# QCopterFCs_Sch.net
KiCad netlist of a schematic drawn in Altium Designer
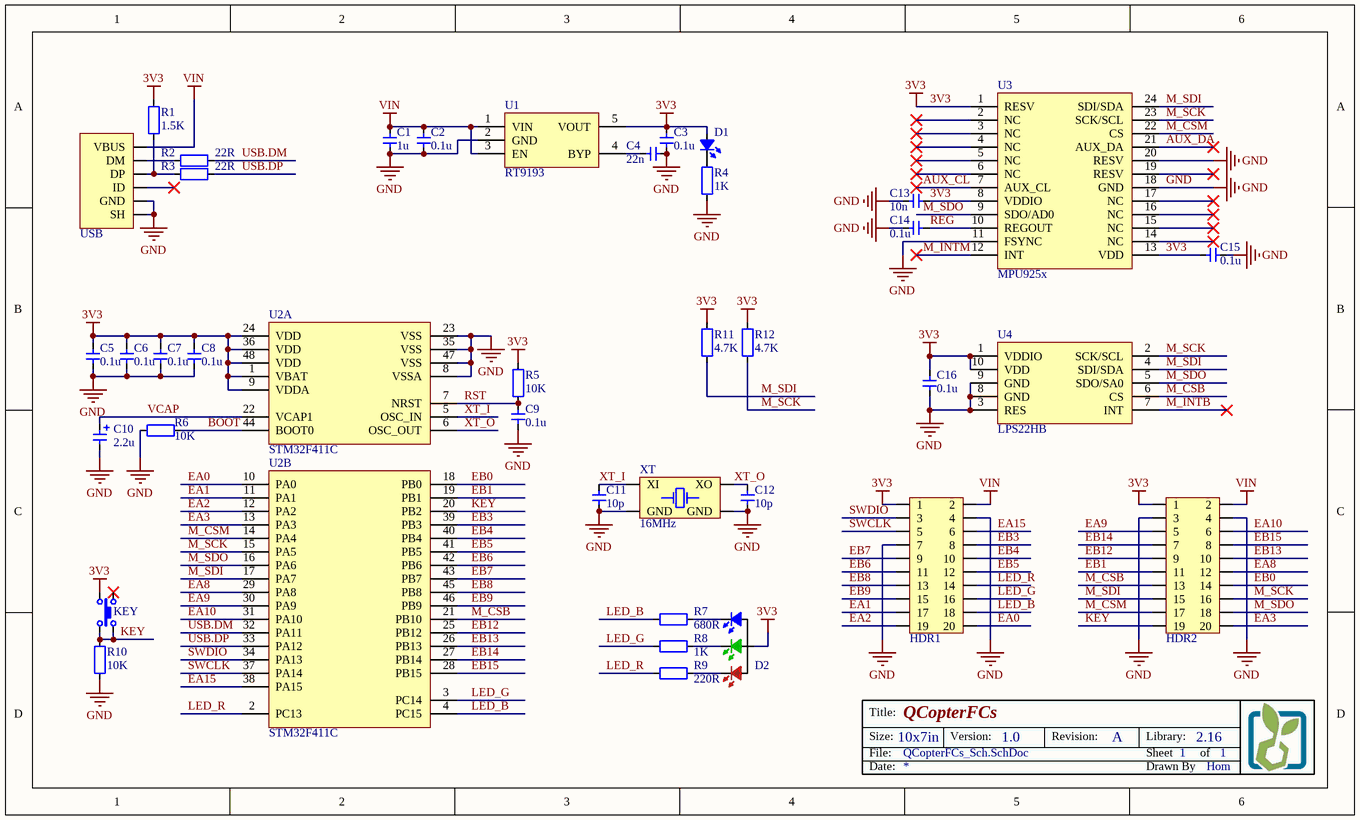
[diagram p0: QCopterFCs_Sch.SchDoc]

(export (version "E")
  (design (tool "Eeschema 10.0.6"))
  (components
    (comp (ref "C1")
      (value "1u")
      (footprint "PCB_PassiveCap:CAP_0603")
      (description "Capacitor")
      (fields (field (name "Comment") "Cap_0603"))
      (libsource (lib "SCH_Passive") (part "Cap_0603"))
    )
    (comp (ref "C2")
      (value "0.1u")
      (footprint "PCB_PassiveCap:CAP_0603")
      (description "Capacitor")
      (fields (field (name "Comment") "Cap_0603"))
      (libsource (lib "SCH_Passive") (part "Cap_0603"))
    )
    (comp (ref "C3")
      (value "0.1u")
      (footprint "PCB_PassiveCap:CAP_0603")
      (description "Capacitor")
      (fields (field (name "Comment") "Cap_0603"))
      (libsource (lib "SCH_Passive") (part "Cap_0603"))
    )
    (comp (ref "C4")
      (value "22n")
      (footprint "PCB_PassiveCap:CAP_0603")
      (description "Capacitor")
      (fields (field (name "Comment") "Cap_0603"))
      (libsource (lib "SCH_Passive") (part "Cap_0603"))
    )
    (comp (ref "C5")
      (value "0.1u")
      (footprint "PCB_PassiveCap:CAP_0402")
      (description "Capacitor")
      (fields (field (name "Comment") "Cap_0402"))
      (libsource (lib "SCH_Passive") (part "Cap_0402"))
    )
    (comp (ref "C6")
      (value "0.1u")
      (footprint "PCB_PassiveCap:CAP_0402")
      (description "Capacitor")
      (fields (field (name "Comment") "Cap_0402"))
      (libsource (lib "SCH_Passive") (part "Cap_0402"))
    )
    (comp (ref "C7")
      (value "0.1u")
      (footprint "PCB_PassiveCap:CAP_0402")
      (description "Capacitor")
      (fields (field (name "Comment") "Cap_0402"))
      (libsource (lib "SCH_Passive") (part "Cap_0402"))
    )
    (comp (ref "C8")
      (value "0.1u")
      (footprint "PCB_PassiveCap:CAP_0402")
      (description "Capacitor")
      (fields (field (name "Comment") "Cap_0402"))
      (libsource (lib "SCH_Passive") (part "Cap_0402"))
    )
    (comp (ref "C9")
      (value "0.1u")
      (footprint "PCB_PassiveCap:CAP_0402")
      (description "Capacitor")
      (fields (field (name "Comment") "Cap_0402"))
      (libsource (lib "SCH_Passive") (part "Cap_0402"))
    )
    (comp (ref "C10")
      (value "2.2u")
      (footprint "PCB_PassiveCap:CAP_TAN_P0805")
      (description "Capacitor")
      (fields (field (name "Comment") "Cap_Tan_0805"))
      (libsource (lib "SCH_Passive") (part "Cap_Tan_0805"))
    )
    (comp (ref "C11")
      (value "10p")
      (footprint "PCB_PassiveCap:CAP_0402")
      (description "Capacitor")
      (fields (field (name "Comment") "Cap_0402"))
      (libsource (lib "SCH_Passive") (part "Cap_0402"))
    )
    (comp (ref "C12")
      (value "10p")
      (footprint "PCB_PassiveCap:CAP_0402")
      (description "Capacitor")
      (fields (field (name "Comment") "Cap_0402"))
      (libsource (lib "SCH_Passive") (part "Cap_0402"))
    )
    (comp (ref "C13")
      (value "10n")
      (footprint "PCB_PassiveCap:CAP_0402")
      (description "Capacitor")
      (fields (field (name "Comment") "Cap_0402"))
      (libsource (lib "SCH_Passive") (part "Cap_0402"))
    )
    (comp (ref "C14")
      (value "0.1u")
      (footprint "PCB_PassiveCap:CAP_0402")
      (description "Capacitor")
      (fields (field (name "Comment") "Cap_0402"))
      (libsource (lib "SCH_Passive") (part "Cap_0402"))
    )
    (comp (ref "C15")
      (value "0.1u")
      (footprint "PCB_PassiveCap:CAP_0402")
      (description "Capacitor")
      (fields (field (name "Comment") "Cap_0402"))
      (libsource (lib "SCH_Passive") (part "Cap_0402"))
    )
    (comp (ref "C16")
      (value "0.1u")
      (footprint "PCB_PassiveCap:CAP_0402")
      (description "Capacitor")
      (fields (field (name "Comment") "Cap_0402"))
      (libsource (lib "SCH_Passive") (part "Cap_0402"))
    )
    (comp (ref "D1")
      (value "LED_0603")
      (footprint "PCB_ActiveLED:LED_0603_YELLOW")
      (description "LED")
      (libsource (lib "SCH_Active") (part "LED_0603"))
    )
    (comp (ref "D2")
      (value "LED_1616_RGB")
      (footprint "PCB_ActiveLED:LED_1616_RGB")
      (description "LED")
      (libsource (lib "SCH_Active") (part "LED_1616_RGB"))
    )
    (comp (ref "HDR1")
      (value "HDR2x10_1.27")
      (footprint "PCB_ConnectorHDR:HDR2X10_1.27_180S")
      (description "Header")
      (libsource (lib "SCH_ConnectorHDR") (part "HDR2x10_1.27"))
    )
    (comp (ref "HDR2")
      (value "HDR2x10_1.27")
      (footprint "PCB_ConnectorHDR:HDR2X10_1.27_180S")
      (description "Header")
      (libsource (lib "SCH_ConnectorHDR") (part "HDR2x10_1.27"))
    )
    (comp (ref "KEY")
      (value "ButtonTACT")
      (footprint "PCB_Switch:ButtonTACT_3.5*3.55_90")
      (description "Button")
      (libsource (lib "SCH_Switch") (part "ButtonTACT"))
    )
    (comp (ref "R1")
      (value "1.5K")
      (footprint "PCB_PassiveRes:RES_0402")
      (description "Resistor")
      (fields (field (name "Comment") "Res_0402"))
      (libsource (lib "") (part "Res_0402_1"))
    )
    (comp (ref "R2")
      (value "22R")
      (footprint "PCB_PassiveRes:RES_0402")
      (description "Resistor")
      (fields (field (name "Comment") "Res_0402"))
      (libsource (lib "") (part "Res_0402_3"))
    )
    (comp (ref "R3")
      (value "22R")
      (footprint "PCB_PassiveRes:RES_0402")
      (description "Resistor")
      (fields (field (name "Comment") "Res_0402"))
      (libsource (lib "") (part "Res_0402_3"))
    )
    (comp (ref "R4")
      (value "1K")
      (footprint "PCB_PassiveRes:RES_0603")
      (description "Resistor")
      (fields (field (name "Comment") "Res_0603"))
      (libsource (lib "SCH_Passive") (part "Res_0603"))
    )
    (comp (ref "R5")
      (value "10K")
      (footprint "PCB_PassiveRes:RES_0402")
      (description "Resistor")
      (fields (field (name "Comment") "Res_0402"))
      (libsource (lib "") (part "Res_0402_2"))
    )
    (comp (ref "R6")
      (value "10K")
      (footprint "PCB_PassiveRes:RES_0402")
      (description "Resistor")
      (fields (field (name "Comment") "Res_0402"))
      (libsource (lib "SCH_Passive") (part "Res_0402"))
    )
    (comp (ref "R7")
      (value "680R")
      (footprint "PCB_PassiveRes:RES_0402")
      (description "Resistor")
      (fields (field (name "Comment") "Res_0402"))
      (libsource (lib "") (part "Res_0402_3"))
    )
    (comp (ref "R8")
      (value "1K")
      (footprint "PCB_PassiveRes:RES_0402")
      (description "Resistor")
      (fields (field (name "Comment") "Res_0402"))
      (libsource (lib "") (part "Res_0402_3"))
    )
    (comp (ref "R9")
      (value "220R")
      (footprint "PCB_PassiveRes:RES_0402")
      (description "Resistor")
      (fields (field (name "Comment") "Res_0402"))
      (libsource (lib "") (part "Res_0402_3"))
    )
    (comp (ref "R10")
      (value "10K")
      (footprint "PCB_PassiveRes:RES_0402")
      (description "Resistor")
      (fields (field (name "Comment") "Res_0402"))
      (libsource (lib "") (part "Res_0402_2"))
    )
    (comp (ref "R11")
      (value "4.7K")
      (footprint "PCB_PassiveRes:RES_0402")
      (description "Resistor")
      (fields (field (name "Comment") "Res_0402"))
      (libsource (lib "") (part "Res_0402_2"))
    )
    (comp (ref "R12")
      (value "4.7K")
      (footprint "PCB_PassiveRes:RES_0402")
      (description "Resistor")
      (fields (field (name "Comment") "Res_0402"))
      (libsource (lib "") (part "Res_0402_2"))
    )
    (comp (ref "U1")
      (value "RT9193")
      (footprint "PCB_IntegratedCircuit:SOT23-5")
      (description "Power")
      (libsource (lib "SCH_IntegratedCircuit") (part "RT9193"))
    )
    (comp (ref "U2")
      (value "STM32F411C")
      (footprint "PCB_IntegratedCircuit:QFN_P0.5_48")
      (description "MCU")
      (libsource (lib "SCH_IntegratedCircuit") (part "STM32F4x1C"))
    )
    (comp (ref "U3")
      (value "MPU925x")
      (footprint "PCB_IntegratedCircuit:QFN_P0.4_24")
      (description "Sensor Motion")
      (libsource (lib "SCH_IntegratedCircuit") (part "MPU925x"))
    )
    (comp (ref "U4")
      (value "LPS22HB")
      (footprint "PCB_IntegratedCircuit:HCLGA-2x2_10")
      (description "Sensor Pressure")
      (libsource (lib "SCH_IntegratedCircuit") (part "LPS22HB"))
    )
    (comp (ref "USB")
      (value "USB_Micro")
      (footprint "PCB_USB:USB_Micro-AB")
      (description "USB")
      (libsource (lib "SCH_USB") (part "USB_Micro"))
    )
    (comp (ref "XT")
      (value "16MHz")
      (footprint "PCB_Oscillator:XT_2520_4")
      (description "Crystal Oscillator")
      (fields (field (name "Comment") "XTAL_2520_4P"))
      (libsource (lib "SCH_Oscillator") (part "XTAL_2520_4P"))
    )
  )
  (nets
    (net (code "1") (name "/AUX_CL") (class "Default")
      (node (ref "U3") (pin "7") (pinfunction "AUX_CL_7") (pintype "passive+no_connect"))
    )
    (net (code "2") (name "/AUX_DA") (class "Default")
      (node (ref "U3") (pin "21") (pinfunction "AUX_DA_21") (pintype "passive+no_connect"))
    )
    (net (code "3") (name "/BOOT") (class "Default")
      (node (ref "R6") (pin "2") (pinfunction "2_2") (pintype "passive"))
      (node (ref "U2") (pin "44") (pinfunction "BOOT0_44") (pintype "passive"))
    )
    (net (code "4") (name "/EA0") (class "Default")
      (node (ref "HDR1") (pin "20") (pinfunction "20_20") (pintype "passive"))
      (node (ref "U2") (pin "10") (pinfunction "PA0_10") (pintype "passive"))
    )
    (net (code "5") (name "/EA1") (class "Default")
      (node (ref "HDR1") (pin "17") (pinfunction "17_17") (pintype "passive"))
      (node (ref "U2") (pin "11") (pinfunction "PA1_11") (pintype "passive"))
    )
    (net (code "6") (name "/EA2") (class "Default")
      (node (ref "HDR1") (pin "19") (pinfunction "19_19") (pintype "passive"))
      (node (ref "U2") (pin "12") (pinfunction "PA2_12") (pintype "passive"))
    )
    (net (code "7") (name "/EA3") (class "Default")
      (node (ref "HDR2") (pin "20") (pinfunction "20_20") (pintype "passive"))
      (node (ref "U2") (pin "13") (pinfunction "PA3_13") (pintype "passive"))
    )
    (net (code "8") (name "/EA8") (class "Default")
      (node (ref "HDR2") (pin "12") (pinfunction "12_12") (pintype "passive"))
      (node (ref "U2") (pin "29") (pinfunction "PA8_29") (pintype "passive"))
    )
    (net (code "9") (name "/EA9") (class "Default")
      (node (ref "HDR2") (pin "5") (pinfunction "5_5") (pintype "passive"))
      (node (ref "U2") (pin "30") (pinfunction "PA9_30") (pintype "passive"))
    )
    (net (code "10") (name "/EA10") (class "Default")
      (node (ref "HDR2") (pin "6") (pinfunction "6_6") (pintype "passive"))
      (node (ref "U2") (pin "31") (pinfunction "PA10_31") (pintype "passive"))
    )
    (net (code "11") (name "/EA15") (class "Default")
      (node (ref "HDR1") (pin "6") (pinfunction "6_6") (pintype "passive"))
      (node (ref "U2") (pin "38") (pinfunction "PA15_38") (pintype "passive"))
    )
    (net (code "12") (name "/EB0") (class "Default")
      (node (ref "HDR2") (pin "14") (pinfunction "14_14") (pintype "passive"))
      (node (ref "U2") (pin "18") (pinfunction "PB0_18") (pintype "passive"))
    )
    (net (code "13") (name "/EB1") (class "Default")
      (node (ref "HDR2") (pin "11") (pinfunction "11_11") (pintype "passive"))
      (node (ref "U2") (pin "19") (pinfunction "PB1_19") (pintype "passive"))
    )
    (net (code "14") (name "/EB3") (class "Default")
      (node (ref "HDR1") (pin "8") (pinfunction "8_8") (pintype "passive"))
      (node (ref "U2") (pin "39") (pinfunction "PB3_39") (pintype "passive"))
    )
    (net (code "15") (name "/EB4") (class "Default")
      (node (ref "HDR1") (pin "10") (pinfunction "10_10") (pintype "passive"))
      (node (ref "U2") (pin "40") (pinfunction "PB4_40") (pintype "passive"))
    )
    (net (code "16") (name "/EB5") (class "Default")
      (node (ref "HDR1") (pin "12") (pinfunction "12_12") (pintype "passive"))
      (node (ref "U2") (pin "41") (pinfunction "PB5_41") (pintype "passive"))
    )
    (net (code "17") (name "/EB6") (class "Default")
      (node (ref "HDR1") (pin "11") (pinfunction "11_11") (pintype "passive"))
      (node (ref "U2") (pin "42") (pinfunction "PB6_42") (pintype "passive"))
    )
    (net (code "18") (name "/EB7") (class "Default")
      (node (ref "HDR1") (pin "9") (pinfunction "9_9") (pintype "passive"))
      (node (ref "U2") (pin "43") (pinfunction "PB7_43") (pintype "passive"))
    )
    (net (code "19") (name "/EB8") (class "Default")
      (node (ref "HDR1") (pin "13") (pinfunction "13_13") (pintype "passive"))
      (node (ref "U2") (pin "45") (pinfunction "PB8_45") (pintype "passive"))
    )
    (net (code "20") (name "/EB9") (class "Default")
      (node (ref "HDR1") (pin "15") (pinfunction "15_15") (pintype "passive"))
      (node (ref "U2") (pin "46") (pinfunction "PB9_46") (pintype "passive"))
    )
    (net (code "21") (name "/EB12") (class "Default")
      (node (ref "HDR2") (pin "9") (pinfunction "9_9") (pintype "passive"))
      (node (ref "U2") (pin "25") (pinfunction "PB12_25") (pintype "passive"))
    )
    (net (code "22") (name "/EB13") (class "Default")
      (node (ref "HDR2") (pin "10") (pinfunction "10_10") (pintype "passive"))
      (node (ref "U2") (pin "26") (pinfunction "PB13_26") (pintype "passive"))
    )
    (net (code "23") (name "/EB14") (class "Default")
      (node (ref "HDR2") (pin "7") (pinfunction "7_7") (pintype "passive"))
      (node (ref "U2") (pin "27") (pinfunction "PB14_27") (pintype "passive"))
    )
    (net (code "24") (name "/EB15") (class "Default")
      (node (ref "HDR2") (pin "8") (pinfunction "8_8") (pintype "passive"))
      (node (ref "U2") (pin "28") (pinfunction "PB15_28") (pintype "passive"))
    )
    (net (code "25") (name "/KEY") (class "Default")
      (node (ref "HDR2") (pin "19") (pinfunction "19_19") (pintype "passive"))
      (node (ref "KEY") (pin "2") (pinfunction "2_2") (pintype "passive"))
      (node (ref "KEY") (pin "4") (pinfunction "4_4") (pintype "passive"))
      (node (ref "R10") (pin "1") (pinfunction "1_1") (pintype "passive"))
      (node (ref "U2") (pin "20") (pinfunction "PB2_20") (pintype "passive"))
    )
    (net (code "26") (name "/LED_B") (class "Default")
      (node (ref "HDR1") (pin "18") (pinfunction "18_18") (pintype "passive"))
      (node (ref "R7") (pin "2") (pinfunction "2_2") (pintype "passive"))
      (node (ref "U2") (pin "4") (pinfunction "PC15_4") (pintype "passive"))
    )
    (net (code "27") (name "/LED_G") (class "Default")
      (node (ref "HDR1") (pin "16") (pinfunction "16_16") (pintype "passive"))
      (node (ref "R8") (pin "2") (pinfunction "2_2") (pintype "passive"))
      (node (ref "U2") (pin "3") (pinfunction "PC14_3") (pintype "passive"))
    )
    (net (code "28") (name "/LED_R") (class "Default")
      (node (ref "HDR1") (pin "14") (pinfunction "14_14") (pintype "passive"))
      (node (ref "R9") (pin "2") (pinfunction "2_2") (pintype "passive"))
      (node (ref "U2") (pin "2") (pinfunction "PC13_2") (pintype "passive"))
    )
    (net (code "29") (name "/M_CSB") (class "Default")
      (node (ref "HDR2") (pin "13") (pinfunction "13_13") (pintype "passive"))
      (node (ref "U2") (pin "21") (pinfunction "PB10_21") (pintype "passive"))
      (node (ref "U4") (pin "6") (pinfunction "CS_6") (pintype "passive"))
    )
    (net (code "30") (name "/M_CSM") (class "Default")
      (node (ref "HDR2") (pin "17") (pinfunction "17_17") (pintype "passive"))
      (node (ref "U2") (pin "14") (pinfunction "PA4_14") (pintype "passive"))
      (node (ref "U3") (pin "22") (pinfunction "CS_22") (pintype "passive"))
    )
    (net (code "31") (name "/M_INTB") (class "Default")
      (node (ref "U4") (pin "7") (pinfunction "INT_7") (pintype "passive+no_connect"))
    )
    (net (code "32") (name "/M_INTM") (class "Default")
      (node (ref "U3") (pin "12") (pinfunction "INT_12") (pintype "passive+no_connect"))
    )
    (net (code "33") (name "/M_SCK") (class "Default")
      (node (ref "HDR2") (pin "16") (pinfunction "16_16") (pintype "passive"))
      (node (ref "R12") (pin "2") (pinfunction "2_2") (pintype "passive"))
      (node (ref "U2") (pin "15") (pinfunction "PA5_15") (pintype "passive"))
      (node (ref "U3") (pin "23") (pinfunction "SCK/SCL_23") (pintype "passive"))
      (node (ref "U4") (pin "2") (pinfunction "SCK/SCL_2") (pintype "passive"))
    )
    (net (code "34") (name "/M_SDI") (class "Default")
      (node (ref "HDR2") (pin "15") (pinfunction "15_15") (pintype "passive"))
      (node (ref "R11") (pin "2") (pinfunction "2_2") (pintype "passive"))
      (node (ref "U2") (pin "17") (pinfunction "PA7_17") (pintype "passive"))
      (node (ref "U3") (pin "24") (pinfunction "SDI/SDA_24") (pintype "passive"))
      (node (ref "U4") (pin "4") (pinfunction "SDI/SDA_4") (pintype "passive"))
    )
    (net (code "35") (name "/M_SDO") (class "Default")
      (node (ref "HDR2") (pin "18") (pinfunction "18_18") (pintype "passive"))
      (node (ref "U2") (pin "16") (pinfunction "PA6_16") (pintype "passive"))
      (node (ref "U3") (pin "9") (pinfunction "SDO/AD0_9") (pintype "passive"))
      (node (ref "U4") (pin "5") (pinfunction "SDO/SA0_5") (pintype "passive"))
    )
    (net (code "36") (name "/REG") (class "Default")
      (node (ref "C14") (pin "1") (pinfunction "1_1") (pintype "passive"))
      (node (ref "U3") (pin "10") (pinfunction "REGOUT_10") (pintype "passive"))
    )
    (net (code "37") (name "/RST") (class "Default")
      (node (ref "C9") (pin "2") (pinfunction "2_2") (pintype "passive"))
      (node (ref "R5") (pin "2") (pinfunction "2_2") (pintype "passive"))
      (node (ref "U2") (pin "7") (pinfunction "NRST_7") (pintype "passive"))
    )
    (net (code "38") (name "/SWCLK") (class "Default")
      (node (ref "HDR1") (pin "5") (pinfunction "5_5") (pintype "passive"))
      (node (ref "U2") (pin "37") (pinfunction "PA14_37") (pintype "passive"))
    )
    (net (code "39") (name "/SWDIO") (class "Default")
      (node (ref "HDR1") (pin "3") (pinfunction "3_3") (pintype "passive"))
      (node (ref "U2") (pin "34") (pinfunction "PA13_34") (pintype "passive"))
    )
    (net (code "40") (name "/USB.DM") (class "Default")
      (node (ref "R2") (pin "1") (pinfunction "1_1") (pintype "passive"))
      (node (ref "U2") (pin "32") (pinfunction "PA11_32") (pintype "passive"))
    )
    (net (code "41") (name "/USB.DP") (class "Default")
      (node (ref "R3") (pin "1") (pinfunction "1_1") (pintype "passive"))
      (node (ref "U2") (pin "33") (pinfunction "PA12_33") (pintype "passive"))
    )
    (net (code "42") (name "/VCAP") (class "Default")
      (node (ref "C10") (pin "1") (pinfunction "1_1") (pintype "passive"))
      (node (ref "U2") (pin "22") (pinfunction "VCAP1_22") (pintype "passive"))
    )
    (net (code "43") (name "/XT_I") (class "Default")
      (node (ref "C11") (pin "2") (pinfunction "2_2") (pintype "passive"))
      (node (ref "U2") (pin "5") (pinfunction "OSC_IN_5") (pintype "passive"))
      (node (ref "XT") (pin "1") (pinfunction "XI_1") (pintype "passive"))
    )
    (net (code "44") (name "/XT_O") (class "Default")
      (node (ref "C12") (pin "2") (pinfunction "2_2") (pintype "passive"))
      (node (ref "U2") (pin "6") (pinfunction "OSC_OUT_6") (pintype "passive"))
      (node (ref "XT") (pin "3") (pinfunction "XO_3") (pintype "passive"))
    )
    (net (code "45") (name "3V3") (class "Default")
      (node (ref "C13") (pin "1") (pinfunction "1_1") (pintype "passive"))
      (node (ref "C15") (pin "2") (pinfunction "2_2") (pintype "passive"))
      (node (ref "C16") (pin "1") (pinfunction "1_1") (pintype "passive"))
      (node (ref "C3") (pin "2") (pinfunction "2_2") (pintype "passive"))
      (node (ref "C5") (pin "2") (pinfunction "2_2") (pintype "passive"))
      (node (ref "C6") (pin "2") (pinfunction "2_2") (pintype "passive"))
      (node (ref "C7") (pin "2") (pinfunction "2_2") (pintype "passive"))
      (node (ref "C8") (pin "2") (pinfunction "2_2") (pintype "passive"))
      (node (ref "D1") (pin "1") (pinfunction "A_1") (pintype "passive"))
      (node (ref "D2") (pin "4") (pinfunction "A_4") (pintype "passive"))
      (node (ref "HDR1") (pin "1") (pinfunction "1_1") (pintype "passive"))
      (node (ref "HDR2") (pin "1") (pinfunction "1_1") (pintype "passive"))
      (node (ref "KEY") (pin "3") (pinfunction "3_3") (pintype "passive"))
      (node (ref "R1") (pin "2") (pinfunction "2_2") (pintype "passive"))
      (node (ref "R11") (pin "1") (pinfunction "1_1") (pintype "passive"))
      (node (ref "R12") (pin "1") (pinfunction "1_1") (pintype "passive"))
      (node (ref "R5") (pin "1") (pinfunction "1_1") (pintype "passive"))
      (node (ref "U1") (pin "5") (pinfunction "VOUT_5") (pintype "passive"))
      (node (ref "U2") (pin "1") (pinfunction "VBAT_1") (pintype "passive"))
      (node (ref "U2") (pin "24") (pinfunction "VDD_24") (pintype "passive"))
      (node (ref "U2") (pin "36") (pinfunction "VDD_36") (pintype "passive"))
      (node (ref "U2") (pin "48") (pinfunction "VDD_48") (pintype "passive"))
      (node (ref "U2") (pin "9") (pinfunction "VDDA_9") (pintype "passive"))
      (node (ref "U3") (pin "1") (pinfunction "RESV_1") (pintype "passive"))
      (node (ref "U3") (pin "13") (pinfunction "VDD_13") (pintype "passive"))
      (node (ref "U3") (pin "8") (pinfunction "VDDIO_8") (pintype "passive"))
      (node (ref "U4") (pin "1") (pinfunction "VDDIO_1") (pintype "passive"))
      (node (ref "U4") (pin "10") (pinfunction "VDD_10") (pintype "passive"))
    )
    (net (code "46") (name "GND") (class "Default")
      (node (ref "C1") (pin "1") (pinfunction "1_1") (pintype "passive"))
      (node (ref "C10") (pin "2") (pinfunction "2_2") (pintype "passive"))
      (node (ref "C11") (pin "1") (pinfunction "1_1") (pintype "passive"))
      (node (ref "C12") (pin "1") (pinfunction "1_1") (pintype "passive"))
      (node (ref "C13") (pin "2") (pinfunction "2_2") (pintype "passive"))
      (node (ref "C14") (pin "2") (pinfunction "2_2") (pintype "passive"))
      (node (ref "C15") (pin "1") (pinfunction "1_1") (pintype "passive"))
      (node (ref "C16") (pin "2") (pinfunction "2_2") (pintype "passive"))
      (node (ref "C2") (pin "1") (pinfunction "1_1") (pintype "passive"))
      (node (ref "C3") (pin "1") (pinfunction "1_1") (pintype "passive"))
      (node (ref "C4") (pin "1") (pinfunction "1_1") (pintype "passive"))
      (node (ref "C5") (pin "1") (pinfunction "1_1") (pintype "passive"))
      (node (ref "C6") (pin "1") (pinfunction "1_1") (pintype "passive"))
      (node (ref "C7") (pin "1") (pinfunction "1_1") (pintype "passive"))
      (node (ref "C8") (pin "1") (pinfunction "1_1") (pintype "passive"))
      (node (ref "C9") (pin "1") (pinfunction "1_1") (pintype "passive"))
      (node (ref "HDR1") (pin "4") (pinfunction "4_4") (pintype "passive"))
      (node (ref "HDR1") (pin "7") (pinfunction "7_7") (pintype "passive"))
      (node (ref "HDR2") (pin "3") (pinfunction "3_3") (pintype "passive"))
      (node (ref "HDR2") (pin "4") (pinfunction "4_4") (pintype "passive"))
      (node (ref "R10") (pin "2") (pinfunction "2_2") (pintype "passive"))
      (node (ref "R4") (pin "1") (pinfunction "1_1") (pintype "passive"))
      (node (ref "R6") (pin "1") (pinfunction "1_1") (pintype "passive"))
      (node (ref "U1") (pin "2") (pinfunction "GND_2") (pintype "passive"))
      (node (ref "U2") (pin "23") (pinfunction "VSS_23") (pintype "passive"))
      (node (ref "U2") (pin "35") (pinfunction "VSS_35") (pintype "passive"))
      (node (ref "U2") (pin "47") (pinfunction "VSS_47") (pintype "passive"))
      (node (ref "U2") (pin "8") (pinfunction "VSSA_8") (pintype "passive"))
      (node (ref "U3") (pin "11") (pinfunction "FSYNC_11") (pintype "passive"))
      (node (ref "U3") (pin "18") (pinfunction "GND_18") (pintype "passive"))
      (node (ref "U3") (pin "20") (pinfunction "RESV_20") (pintype "passive"))
      (node (ref "U4") (pin "3") (pinfunction "RES_3") (pintype "passive"))
      (node (ref "U4") (pin "8") (pinfunction "GND_8") (pintype "passive"))
      (node (ref "U4") (pin "9") (pinfunction "GND_9") (pintype "passive"))
      (node (ref "USB") (pin "0") (pinfunction "SH_0") (pintype "passive"))
      (node (ref "USB") (pin "5") (pinfunction "GND_5") (pintype "passive"))
      (node (ref "XT") (pin "2") (pinfunction "GND_2") (pintype "passive"))
      (node (ref "XT") (pin "4") (pinfunction "GND_4") (pintype "passive"))
    )
    (net (code "47") (name "Net-(D1-K)") (class "Default")
      (node (ref "D1") (pin "2") (pinfunction "K_2") (pintype "passive"))
      (node (ref "R4") (pin "2") (pinfunction "2_2") (pintype "passive"))
    )
    (net (code "48") (name "Net-(D2-B)") (class "Default")
      (node (ref "D2") (pin "3") (pinfunction "B_3") (pintype "passive"))
      (node (ref "R7") (pin "1") (pinfunction "1_1") (pintype "passive"))
    )
    (net (code "49") (name "Net-(D2-G)") (class "Default")
      (node (ref "D2") (pin "2") (pinfunction "G_2") (pintype "passive"))
      (node (ref "R8") (pin "1") (pinfunction "1_1") (pintype "passive"))
    )
    (net (code "50") (name "Net-(D2-R)") (class "Default")
      (node (ref "D2") (pin "1") (pinfunction "R_1") (pintype "passive"))
      (node (ref "R9") (pin "1") (pinfunction "1_1") (pintype "passive"))
    )
    (net (code "51") (name "Net-(U1-BYP)") (class "Default")
      (node (ref "C4") (pin "2") (pinfunction "2_2") (pintype "passive"))
      (node (ref "U1") (pin "4") (pinfunction "BYP_4") (pintype "passive"))
    )
    (net (code "52") (name "Net-(USB-DM)") (class "Default")
      (node (ref "R2") (pin "2") (pinfunction "2_2") (pintype "passive"))
      (node (ref "USB") (pin "2") (pinfunction "DM_2") (pintype "passive"))
    )
    (net (code "53") (name "Net-(USB-DP)") (class "Default")
      (node (ref "R1") (pin "1") (pinfunction "1_1") (pintype "passive"))
      (node (ref "R3") (pin "2") (pinfunction "2_2") (pintype "passive"))
      (node (ref "USB") (pin "3") (pinfunction "DP_3") (pintype "passive"))
    )
    (net (code "54") (name "VIN") (class "Default")
      (node (ref "C1") (pin "2") (pinfunction "2_2") (pintype "passive"))
      (node (ref "C2") (pin "2") (pinfunction "2_2") (pintype "passive"))
      (node (ref "HDR1") (pin "2") (pinfunction "2_2") (pintype "passive"))
      (node (ref "HDR2") (pin "2") (pinfunction "2_2") (pintype "passive"))
      (node (ref "U1") (pin "1") (pinfunction "VIN_1") (pintype "passive"))
      (node (ref "U1") (pin "3") (pinfunction "EN_3") (pintype "power_in"))
      (node (ref "USB") (pin "1") (pinfunction "VBUS_1") (pintype "passive"))
    )
    (net (code "55") (name "unconnected-(KEY-Pad1)") (class "Default")
      (node (ref "KEY") (pin "1") (pinfunction "1_1") (pintype "passive+no_connect"))
    )
    (net (code "56") (name "unconnected-(U3-NC-Pad2)") (class "Default")
      (node (ref "U3") (pin "2") (pinfunction "NC_2") (pintype "passive+no_connect"))
    )
    (net (code "57") (name "unconnected-(U3-NC-Pad3)") (class "Default")
      (node (ref "U3") (pin "3") (pinfunction "NC_3") (pintype "passive+no_connect"))
    )
    (net (code "58") (name "unconnected-(U3-NC-Pad4)") (class "Default")
      (node (ref "U3") (pin "4") (pinfunction "NC_4") (pintype "passive+no_connect"))
    )
    (net (code "59") (name "unconnected-(U3-NC-Pad5)") (class "Default")
      (node (ref "U3") (pin "5") (pinfunction "NC_5") (pintype "passive+no_connect"))
    )
    (net (code "60") (name "unconnected-(U3-NC-Pad6)") (class "Default")
      (node (ref "U3") (pin "6") (pinfunction "NC_6") (pintype "passive+no_connect"))
    )
    (net (code "61") (name "unconnected-(U3-NC-Pad14)") (class "Default")
      (node (ref "U3") (pin "14") (pinfunction "NC_14") (pintype "passive+no_connect"))
    )
    (net (code "62") (name "unconnected-(U3-NC-Pad15)") (class "Default")
      (node (ref "U3") (pin "15") (pinfunction "NC_15") (pintype "passive+no_connect"))
    )
    (net (code "63") (name "unconnected-(U3-NC-Pad16)") (class "Default")
      (node (ref "U3") (pin "16") (pinfunction "NC_16") (pintype "passive+no_connect"))
    )
    (net (code "64") (name "unconnected-(U3-NC-Pad17)") (class "Default")
      (node (ref "U3") (pin "17") (pinfunction "NC_17") (pintype "passive+no_connect"))
    )
    (net (code "65") (name "unconnected-(U3-RESV-Pad19)") (class "Default")
      (node (ref "U3") (pin "19") (pinfunction "RESV_19") (pintype "passive+no_connect"))
    )
    (net (code "66") (name "unconnected-(USB-ID-Pad4)") (class "Default")
      (node (ref "USB") (pin "4") (pinfunction "ID_4") (pintype "passive+no_connect"))
    )
  )
)
